# DACv3-Controller.net
KiCad netlist of a schematic drawn in EAGLE
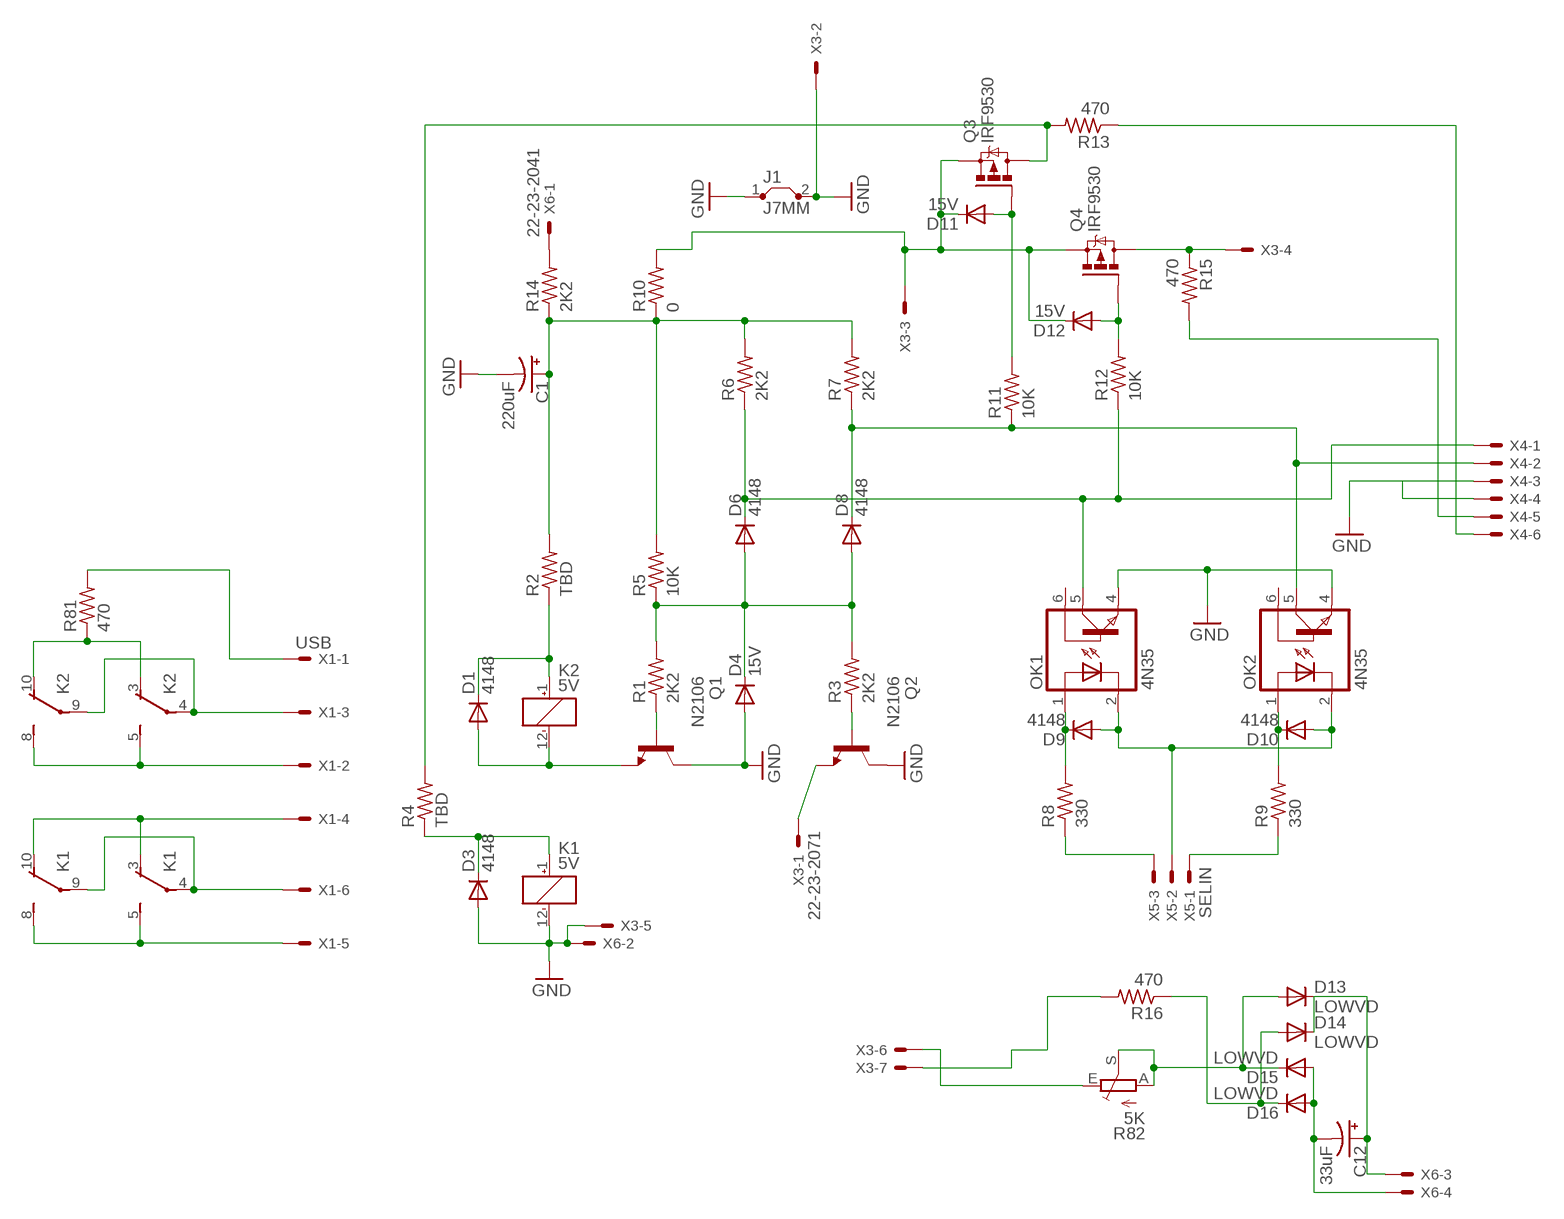
[diagram p0: schematic, sheet 1]

(export (version "E")
  (design (tool "Eeschema 10.0.6"))
  (components
    (comp (ref "C1")
      (value "220uF")
      (footprint "eagle-import:E5-10,5")
      (libsource (lib "eagle-import") (part "CPOL-USE5-10.5"))
    )
    (comp (ref "C12")
      (value "33uF")
      (footprint "eagle-import:TAP5-60")
      (libsource (lib "eagle-import") (part "CPOL-USTAP5-60"))
    )
    (comp (ref "D1")
      (value "4148")
      (footprint "eagle-import:DO35-7")
      (libsource (lib "eagle-import") (part "1N4148DO35-7"))
    )
    (comp (ref "D3")
      (value "4148")
      (footprint "eagle-import:DO35-7")
      (libsource (lib "eagle-import") (part "1N4148DO35-7"))
    )
    (comp (ref "D4")
      (value "15V")
      (footprint "eagle-import:DO35-7")
      (libsource (lib "eagle-import") (part "1N4148DO35-7"))
    )
    (comp (ref "D6")
      (value "4148")
      (footprint "eagle-import:DO35-7")
      (libsource (lib "eagle-import") (part "1N4148DO35-7"))
    )
    (comp (ref "D8")
      (value "4148")
      (footprint "eagle-import:DO35-7")
      (libsource (lib "eagle-import") (part "1N4148DO35-7"))
    )
    (comp (ref "D9")
      (value "4148")
      (footprint "eagle-import:DO35-7")
      (libsource (lib "eagle-import") (part "1N4148DO35-7"))
    )
    (comp (ref "D10")
      (value "4148")
      (footprint "eagle-import:DO35-7")
      (libsource (lib "eagle-import") (part "1N4148DO35-7"))
    )
    (comp (ref "D11")
      (value "15V")
      (footprint "eagle-import:DO35-7")
      (libsource (lib "eagle-import") (part "1N4148DO35-7"))
    )
    (comp (ref "D12")
      (value "15V")
      (footprint "eagle-import:DO35-7")
      (libsource (lib "eagle-import") (part "1N4148DO35-7"))
    )
    (comp (ref "D13")
      (value "LOWVD")
      (footprint "eagle-import:DO35-7")
      (libsource (lib "eagle-import") (part "1N4148DO35-7"))
    )
    (comp (ref "D14")
      (value "LOWVD")
      (footprint "eagle-import:DO35-7")
      (libsource (lib "eagle-import") (part "1N4148DO35-7"))
    )
    (comp (ref "D15")
      (value "LOWVD")
      (footprint "eagle-import:DO35-7")
      (libsource (lib "eagle-import") (part "1N4148DO35-7"))
    )
    (comp (ref "D16")
      (value "LOWVD")
      (footprint "eagle-import:DO35-7")
      (libsource (lib "eagle-import") (part "1N4148DO35-7"))
    )
    (comp (ref "J1")
      (value "J7MM")
      (footprint "eagle-import:07")
      (libsource (lib "eagle-import") (part "J7MM"))
    )
    (comp (ref "K1")
      (value "5V")
      (footprint "eagle-import:TX2")
      (fields
        (field (name "MF") "AROMAT/ MATSUSHITA")
        (field (name "MPN") "TX2-12V")
        (field (name "MF_1") "AROMAT/ MATSUSHITA")
        (field (name "MPN_1") "TX2-12V")
        (field (name "OC_FARNELL") "1200952")
        (field (name "OC_NEWARK") "67K1295")
      )
      (libsource (lib "eagle-import") (part "TX2?-12V"))
    )
    (comp (ref "K2")
      (value "5V")
      (footprint "eagle-import:TX2")
      (fields
        (field (name "MF") "AROMAT/ MATSUSHITA")
        (field (name "MPN") "TX2-12V")
        (field (name "MF_1") "AROMAT/ MATSUSHITA")
        (field (name "MPN_1") "TX2-12V")
        (field (name "OC_FARNELL") "1200952")
        (field (name "OC_NEWARK") "67K1295")
      )
      (libsource (lib "eagle-import") (part "TX2?-12V"))
    )
    (comp (ref "OK1")
      (value "4N35")
      (footprint "eagle-import:DIL06")
      (fields (field (name "MF") "FAIRCHILD SEMICONDUCTOR"))
      (libsource (lib "eagle-import") (part "4N35"))
    )
    (comp (ref "OK2")
      (value "4N35")
      (footprint "eagle-import:DIL06")
      (fields (field (name "MF") "FAIRCHILD SEMICONDUCTOR"))
      (libsource (lib "eagle-import") (part "4N35"))
    )
    (comp (ref "Q1")
      (value "N2106")
      (footprint "eagle-import:TO92-EBC")
      (libsource (lib "eagle-import") (part "BC550B"))
    )
    (comp (ref "Q2")
      (value "N2106")
      (footprint "eagle-import:TO92-EBC")
      (libsource (lib "eagle-import") (part "BC550B"))
    )
    (comp (ref "Q3")
      (value "IRF9530")
      (footprint "eagle-import:TO220BV")
      (libsource (lib "eagle-import") (part "IRF9530"))
    )
    (comp (ref "Q4")
      (value "IRF9530")
      (footprint "eagle-import:TO220BV")
      (libsource (lib "eagle-import") (part "IRF9530"))
    )
    (comp (ref "R1")
      (value "2K2")
      (footprint "eagle-import:0207_10")
      (libsource (lib "eagle-import") (part "R-US_0207/10"))
    )
    (comp (ref "R2")
      (value "TBD")
      (footprint "eagle-import:0207_10")
      (libsource (lib "eagle-import") (part "R-US_0207/10"))
    )
    (comp (ref "R3")
      (value "2K2")
      (footprint "eagle-import:0207_10")
      (libsource (lib "eagle-import") (part "R-US_0207/10"))
    )
    (comp (ref "R4")
      (value "TBD")
      (footprint "eagle-import:0207_10")
      (libsource (lib "eagle-import") (part "R-US_0207/10"))
    )
    (comp (ref "R5")
      (value "10K")
      (footprint "eagle-import:0207_10")
      (libsource (lib "eagle-import") (part "R-US_0207/10"))
    )
    (comp (ref "R6")
      (value "2K2")
      (footprint "eagle-import:0207_10")
      (libsource (lib "eagle-import") (part "R-US_0207/10"))
    )
    (comp (ref "R7")
      (value "2K2")
      (footprint "eagle-import:0207_10")
      (libsource (lib "eagle-import") (part "R-US_0207/10"))
    )
    (comp (ref "R8")
      (value "330")
      (footprint "eagle-import:0207_10")
      (libsource (lib "eagle-import") (part "R-US_0207/10"))
    )
    (comp (ref "R9")
      (value "330")
      (footprint "eagle-import:0207_10")
      (libsource (lib "eagle-import") (part "R-US_0207/10"))
    )
    (comp (ref "R10")
      (value "0")
      (footprint "eagle-import:0207_12")
      (libsource (lib "eagle-import") (part "R-US_0207/12"))
    )
    (comp (ref "R11")
      (value "10K")
      (footprint "eagle-import:0207_10")
      (libsource (lib "eagle-import") (part "R-US_0207/10"))
    )
    (comp (ref "R12")
      (value "10K")
      (footprint "eagle-import:0207_10")
      (libsource (lib "eagle-import") (part "R-US_0207/10"))
    )
    (comp (ref "R13")
      (value "470")
      (footprint "eagle-import:0207_10")
      (libsource (lib "eagle-import") (part "R-US_0207/10"))
    )
    (comp (ref "R14")
      (value "2K2")
      (footprint "eagle-import:0207_12")
      (libsource (lib "eagle-import") (part "R-US_0207/12"))
    )
    (comp (ref "R15")
      (value "470")
      (footprint "eagle-import:0207_10")
      (libsource (lib "eagle-import") (part "R-US_0207/10"))
    )
    (comp (ref "R16")
      (value "470")
      (footprint "eagle-import:0207_10")
      (libsource (lib "eagle-import") (part "R-US_0207/10"))
    )
    (comp (ref "R81")
      (value "470")
      (footprint "eagle-import:0207_10")
      (libsource (lib "eagle-import") (part "R-US_0207/10"))
    )
    (comp (ref "R82")
      (value "5K")
      (footprint "eagle-import:RJ9W")
      (libsource (lib "eagle-import") (part "TRIM_EU-RJ9W"))
    )
    (comp (ref "X1")
      (value "USB")
      (footprint "eagle-import:22-23-2061")
      (fields (field (name "MF") "MOLEX") (field (name "MPN") "22-23-2061"))
      (libsource (lib "eagle-import") (part "22-23-2061"))
    )
    (comp (ref "X3")
      (value "22-23-2071")
      (footprint "eagle-import:22-23-2071")
      (fields (field (name "MF") "MOLEX"))
      (libsource (lib "eagle-import") (part "22-23-2071"))
    )
    (comp (ref "X4")
      (value "22-23-2061")
      (footprint "eagle-import:22-23-2061")
      (fields (field (name "MF") "MOLEX"))
      (libsource (lib "eagle-import") (part "22-23-2061"))
    )
    (comp (ref "X5")
      (value "SELIN")
      (footprint "eagle-import:22-23-2031")
      (fields (field (name "MF") "MOLEX") (field (name "MPN") "22-23-2031"))
      (libsource (lib "eagle-import") (part "22-23-2031"))
    )
    (comp (ref "X6")
      (value "22-23-2041")
      (footprint "eagle-import:22-23-2041")
      (fields (field (name "MF") "MOLEX"))
      (libsource (lib "eagle-import") (part "22-23-2041"))
    )
  )
  (nets
    (net (code "1") (name "GND") (class "Default")
      (node (ref "C1") (pin "-") (pinfunction "-_-") (pintype "passive"))
      (node (ref "D3") (pin "A") (pinfunction "A_A") (pintype "passive"))
      (node (ref "D4") (pin "A") (pinfunction "A_A") (pintype "passive"))
      (node (ref "J1") (pin "1") (pinfunction "1_1") (pintype "passive"))
      (node (ref "J1") (pin "2") (pinfunction "2_2") (pintype "passive"))
      (node (ref "K1") (pin "12") (pinfunction "-_12") (pintype "passive"))
      (node (ref "OK1") (pin "4") (pinfunction "EMI_4") (pintype "passive"))
      (node (ref "OK2") (pin "4") (pinfunction "EMI_4") (pintype "passive"))
      (node (ref "Q1") (pin "C") (pinfunction "C_C") (pintype "passive"))
      (node (ref "Q2") (pin "C") (pinfunction "C_C") (pintype "passive"))
      (node (ref "X3") (pin "2") (pinfunction "S_2") (pintype "passive"))
      (node (ref "X3") (pin "5") (pinfunction "S_5") (pintype "passive"))
      (node (ref "X4") (pin "3") (pinfunction "S_3") (pintype "passive"))
      (node (ref "X4") (pin "4") (pinfunction "S_4") (pintype "passive"))
      (node (ref "X6") (pin "2") (pinfunction "S_2") (pintype "passive"))
    )
    (net (code "2") (name "Net-(C1-Pad+)") (class "Default")
      (node (ref "C1") (pin "+") (pinfunction "+_+") (pintype "passive"))
      (node (ref "R10") (pin "1") (pinfunction "1_1") (pintype "passive"))
      (node (ref "R14") (pin "1") (pinfunction "1_1") (pintype "passive"))
      (node (ref "R2") (pin "2") (pinfunction "2_2") (pintype "passive"))
      (node (ref "R5") (pin "2") (pinfunction "2_2") (pintype "passive"))
      (node (ref "R6") (pin "2") (pinfunction "2_2") (pintype "passive"))
      (node (ref "R7") (pin "2") (pinfunction "2_2") (pintype "passive"))
    )
    (net (code "3") (name "Net-(D4-PadC)") (class "Default")
      (node (ref "D4") (pin "C") (pinfunction "C_C") (pintype "passive"))
      (node (ref "D6") (pin "A") (pinfunction "A_A") (pintype "passive"))
      (node (ref "D8") (pin "A") (pinfunction "A_A") (pintype "passive"))
      (node (ref "R1") (pin "2") (pinfunction "2_2") (pintype "passive"))
      (node (ref "R3") (pin "2") (pinfunction "2_2") (pintype "passive"))
      (node (ref "R5") (pin "1") (pinfunction "1_1") (pintype "passive"))
    )
    (net (code "4") (name "Net-(D11-PadA)") (class "Default")
      (node (ref "D11") (pin "A") (pinfunction "A_A") (pintype "passive"))
      (node (ref "Q3") (pin "G") (pinfunction "G_G") (pintype "passive"))
      (node (ref "R11") (pin "2") (pinfunction "2_2") (pintype "passive"))
    )
    (net (code "5") (name "Net-(D12-PadA)") (class "Default")
      (node (ref "D12") (pin "A") (pinfunction "A_A") (pintype "passive"))
      (node (ref "Q4") (pin "G") (pinfunction "G_G") (pintype "passive"))
      (node (ref "R12") (pin "2") (pinfunction "2_2") (pintype "passive"))
    )
    (net (code "6") (name "Net-(D13-PadA)") (class "Default")
      (node (ref "D13") (pin "A") (pinfunction "A_A") (pintype "passive"))
      (node (ref "D15") (pin "C") (pinfunction "C_C") (pintype "passive"))
      (node (ref "R82") (pin "A") (pinfunction "A_A") (pintype "passive"))
      (node (ref "R82") (pin "S") (pinfunction "S_S") (pintype "passive"))
    )
    (net (code "7") (name "Net-(D14-PadA)") (class "Default")
      (node (ref "D14") (pin "A") (pinfunction "A_A") (pintype "passive"))
      (node (ref "D16") (pin "C") (pinfunction "C_C") (pintype "passive"))
      (node (ref "R16") (pin "1") (pinfunction "1_1") (pintype "passive"))
    )
    (net (code "8") (name "Net-(K1A-O)") (class "Default")
      (node (ref "K1") (pin "10") (pinfunction "O_10") (pintype "passive"))
      (node (ref "K1") (pin "3") (pinfunction "O_3") (pintype "passive"))
      (node (ref "X1") (pin "4") (pinfunction "S_4") (pintype "passive"))
    )
    (net (code "9") (name "Net-(K1A-P)") (class "Default")
      (node (ref "K1") (pin "4") (pinfunction "P_4") (pintype "passive"))
      (node (ref "K1") (pin "9") (pinfunction "P_9") (pintype "passive"))
      (node (ref "X1") (pin "6") (pinfunction "S_6") (pintype "passive"))
    )
    (net (code "10") (name "Net-(K1A-S)") (class "Default")
      (node (ref "K1") (pin "5") (pinfunction "S_5") (pintype "passive"))
      (node (ref "K1") (pin "8") (pinfunction "S_8") (pintype "passive"))
      (node (ref "X1") (pin "5") (pinfunction "S_5") (pintype "passive"))
    )
    (net (code "11") (name "Net-(K1C-+)") (class "Default")
      (node (ref "D3") (pin "C") (pinfunction "C_C") (pintype "passive"))
      (node (ref "K1") (pin "1") (pinfunction "+_1") (pintype "passive"))
      (node (ref "R4") (pin "1") (pinfunction "1_1") (pintype "passive"))
    )
    (net (code "12") (name "Net-(K2A-O)") (class "Default")
      (node (ref "K2") (pin "10") (pinfunction "O_10") (pintype "passive"))
      (node (ref "K2") (pin "3") (pinfunction "O_3") (pintype "passive"))
      (node (ref "R81") (pin "1") (pinfunction "1_1") (pintype "passive"))
    )
    (net (code "13") (name "Net-(K2A-P)") (class "Default")
      (node (ref "K2") (pin "4") (pinfunction "P_4") (pintype "passive"))
      (node (ref "K2") (pin "9") (pinfunction "P_9") (pintype "passive"))
      (node (ref "X1") (pin "3") (pinfunction "S_3") (pintype "passive"))
    )
    (net (code "14") (name "Net-(K2A-S)") (class "Default")
      (node (ref "K2") (pin "5") (pinfunction "S_5") (pintype "passive"))
      (node (ref "K2") (pin "8") (pinfunction "S_8") (pintype "passive"))
      (node (ref "X1") (pin "2") (pinfunction "S_2") (pintype "passive"))
    )
    (net (code "15") (name "Net-(K2C-+)") (class "Default")
      (node (ref "D1") (pin "C") (pinfunction "C_C") (pintype "passive"))
      (node (ref "K2") (pin "1") (pinfunction "+_1") (pintype "passive"))
      (node (ref "R2") (pin "1") (pinfunction "1_1") (pintype "passive"))
    )
    (net (code "16") (name "Net-(K2C--)") (class "Default")
      (node (ref "D1") (pin "A") (pinfunction "A_A") (pintype "passive"))
      (node (ref "K2") (pin "12") (pinfunction "-_12") (pintype "passive"))
      (node (ref "Q1") (pin "E") (pinfunction "E_E") (pintype "passive"))
    )
    (net (code "17") (name "Net-(OK1-A)") (class "Default")
      (node (ref "D9") (pin "C") (pinfunction "C_C") (pintype "passive"))
      (node (ref "OK1") (pin "1") (pinfunction "A_1") (pintype "passive"))
      (node (ref "R8") (pin "2") (pinfunction "2_2") (pintype "passive"))
    )
    (net (code "18") (name "Net-(OK1-C)") (class "Default")
      (node (ref "D10") (pin "A") (pinfunction "A_A") (pintype "passive"))
      (node (ref "D9") (pin "A") (pinfunction "A_A") (pintype "passive"))
      (node (ref "OK1") (pin "2") (pinfunction "C_2") (pintype "passive"))
      (node (ref "OK2") (pin "2") (pinfunction "C_2") (pintype "passive"))
      (node (ref "X5") (pin "2") (pinfunction "S_2") (pintype "passive"))
    )
    (net (code "19") (name "Net-(OK1-COL)") (class "Default")
      (node (ref "D6") (pin "C") (pinfunction "C_C") (pintype "passive"))
      (node (ref "OK1") (pin "5") (pinfunction "COL_5") (pintype "passive"))
      (node (ref "R12") (pin "1") (pinfunction "1_1") (pintype "passive"))
      (node (ref "R6") (pin "1") (pinfunction "1_1") (pintype "passive"))
      (node (ref "X4") (pin "1") (pinfunction "S_1") (pintype "passive"))
    )
    (net (code "20") (name "Net-(OK2-A)") (class "Default")
      (node (ref "D10") (pin "C") (pinfunction "C_C") (pintype "passive"))
      (node (ref "OK2") (pin "1") (pinfunction "A_1") (pintype "passive"))
      (node (ref "R9") (pin "2") (pinfunction "2_2") (pintype "passive"))
    )
    (net (code "21") (name "Net-(OK2-COL)") (class "Default")
      (node (ref "D8") (pin "C") (pinfunction "C_C") (pintype "passive"))
      (node (ref "OK2") (pin "5") (pinfunction "COL_5") (pintype "passive"))
      (node (ref "R11") (pin "1") (pinfunction "1_1") (pintype "passive"))
      (node (ref "R7") (pin "1") (pinfunction "1_1") (pintype "passive"))
      (node (ref "X4") (pin "2") (pinfunction "S_2") (pintype "passive"))
    )
    (net (code "22") (name "Net-(Q1-PadB)") (class "Default")
      (node (ref "Q1") (pin "B") (pinfunction "B_B") (pintype "passive"))
      (node (ref "R1") (pin "1") (pinfunction "1_1") (pintype "passive"))
    )
    (net (code "23") (name "Net-(Q2-PadB)") (class "Default")
      (node (ref "Q2") (pin "B") (pinfunction "B_B") (pintype "passive"))
      (node (ref "R3") (pin "1") (pinfunction "1_1") (pintype "passive"))
    )
    (net (code "24") (name "Net-(Q3-PadD)") (class "Default")
      (node (ref "Q3") (pin "D") (pinfunction "D_D") (pintype "passive"))
      (node (ref "R13") (pin "2") (pinfunction "2_2") (pintype "passive"))
      (node (ref "R4") (pin "2") (pinfunction "2_2") (pintype "passive"))
    )
    (net (code "25") (name "Net-(X1A-S)") (class "Default")
      (node (ref "R81") (pin "2") (pinfunction "2_2") (pintype "passive"))
      (node (ref "X1") (pin "1") (pinfunction "S_1") (pintype "passive"))
    )
    (net (code "26") (name "Net-(X3A-S)") (class "Default")
      (node (ref "Q2") (pin "E") (pinfunction "E_E") (pintype "passive"))
      (node (ref "X3") (pin "1") (pinfunction "S_1") (pintype "passive"))
    )
    (net (code "27") (name "Net-(X3C-S)") (class "Default")
      (node (ref "D11") (pin "C") (pinfunction "C_C") (pintype "passive"))
      (node (ref "D12") (pin "C") (pinfunction "C_C") (pintype "passive"))
      (node (ref "Q3") (pin "S") (pinfunction "S_S") (pintype "passive"))
      (node (ref "Q4") (pin "S") (pinfunction "S_S") (pintype "passive"))
      (node (ref "R10") (pin "2") (pinfunction "2_2") (pintype "passive"))
      (node (ref "X3") (pin "3") (pinfunction "S_3") (pintype "passive"))
    )
    (net (code "28") (name "Net-(X3D-S)") (class "Default")
      (node (ref "Q4") (pin "D") (pinfunction "D_D") (pintype "passive"))
      (node (ref "R15") (pin "1") (pinfunction "1_1") (pintype "passive"))
      (node (ref "X3") (pin "4") (pinfunction "S_4") (pintype "passive"))
    )
    (net (code "29") (name "Net-(X3F-S)") (class "Default")
      (node (ref "R82") (pin "E") (pinfunction "E_E") (pintype "passive"))
      (node (ref "X3") (pin "6") (pinfunction "S_6") (pintype "passive"))
    )
    (net (code "30") (name "Net-(X3G-S)") (class "Default")
      (node (ref "R16") (pin "2") (pinfunction "2_2") (pintype "passive"))
      (node (ref "X3") (pin "7") (pinfunction "S_7") (pintype "passive"))
    )
    (net (code "31") (name "Net-(X4E-S)") (class "Default")
      (node (ref "R15") (pin "2") (pinfunction "2_2") (pintype "passive"))
      (node (ref "X4") (pin "5") (pinfunction "S_5") (pintype "passive"))
    )
    (net (code "32") (name "Net-(X4F-S)") (class "Default")
      (node (ref "R13") (pin "1") (pinfunction "1_1") (pintype "passive"))
      (node (ref "X4") (pin "6") (pinfunction "S_6") (pintype "passive"))
    )
    (net (code "33") (name "Net-(X5A-S)") (class "Default")
      (node (ref "R9") (pin "1") (pinfunction "1_1") (pintype "passive"))
      (node (ref "X5") (pin "1") (pinfunction "S_1") (pintype "passive"))
    )
    (net (code "34") (name "Net-(X5C-S)") (class "Default")
      (node (ref "R8") (pin "1") (pinfunction "1_1") (pintype "passive"))
      (node (ref "X5") (pin "3") (pinfunction "S_3") (pintype "passive"))
    )
    (net (code "35") (name "Net-(X6A-S)") (class "Default")
      (node (ref "R14") (pin "2") (pinfunction "2_2") (pintype "passive"))
      (node (ref "X6") (pin "1") (pinfunction "S_1") (pintype "passive"))
    )
    (net (code "36") (name "Net-(X6C-S)") (class "Default")
      (node (ref "C12") (pin "+") (pinfunction "+_+") (pintype "passive"))
      (node (ref "D13") (pin "C") (pinfunction "C_C") (pintype "passive"))
      (node (ref "D14") (pin "C") (pinfunction "C_C") (pintype "passive"))
      (node (ref "X6") (pin "3") (pinfunction "S_3") (pintype "passive"))
    )
    (net (code "37") (name "Net-(X6D-S)") (class "Default")
      (node (ref "C12") (pin "-") (pinfunction "-_-") (pintype "passive"))
      (node (ref "D15") (pin "A") (pinfunction "A_A") (pintype "passive"))
      (node (ref "D16") (pin "A") (pinfunction "A_A") (pintype "passive"))
      (node (ref "X6") (pin "4") (pinfunction "S_4") (pintype "passive"))
    )
    (net (code "38") (name "unconnected-(OK1-BAS-Pad6)") (class "Default")
      (node (ref "OK1") (pin "6") (pinfunction "BAS_6") (pintype "passive"))
    )
    (net (code "39") (name "unconnected-(OK2-BAS-Pad6)") (class "Default")
      (node (ref "OK2") (pin "6") (pinfunction "BAS_6") (pintype "passive"))
    )
  )
)
